# PWR-LM2941S.net
KiCad netlist of a schematic drawn in Altium Designer
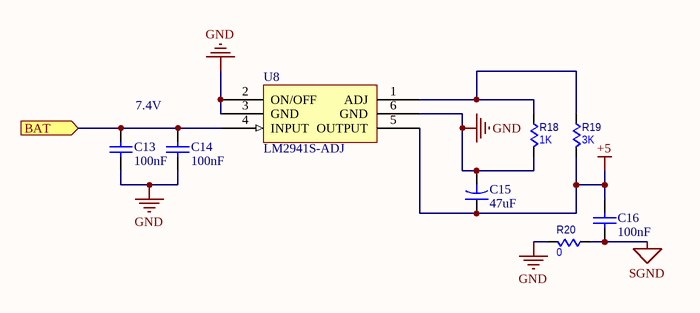
[diagram p0: PWR-LM2941S.SchDoc]

(export (version "E")
  (design (tool "Eeschema 10.0.6"))
  (components
    (comp (ref "C13")
      (value "100nF")
      (footprint "0603")
      (description "无极性电容")
      (fields (field (name "Comment") "Cap") (field (name "PUBLISHER") "Altium Limited"))
      (libsource (lib "haoze") (part "Cap"))
    )
    (comp (ref "C14")
      (value "100nF")
      (footprint "0603")
      (description "无极性电容")
      (fields (field (name "Comment") "Cap") (field (name "PUBLISHER") "Altium Limited"))
      (libsource (lib "haoze") (part "Cap"))
    )
    (comp (ref "C15")
      (value "47uF")
      (footprint "Cap-47uF")
      (description "Capacitor")
      (fields (field (name "Comment") "Cap Pol") (field (name "PUBLISHER") "Altium Limited"))
      (libsource (lib "haoze") (part "Cap Pol"))
    )
    (comp (ref "C16")
      (value "100nF")
      (footprint "0603")
      (description "无极性电容")
      (fields (field (name "Comment") "Cap") (field (name "PUBLISHER") "Altium Limited"))
      (libsource (lib "haoze") (part "Cap"))
    )
    (comp (ref "R18")
      (value "1K")
      (footprint "0603")
      (description "常规电阻")
      (fields (field (name "Comment") "Res"))
      (libsource (lib "haoze") (part "Res"))
    )
    (comp (ref "R19")
      (value "3K")
      (footprint "0603")
      (description "常规电阻")
      (fields (field (name "Comment") "Res"))
      (libsource (lib "haoze") (part "Res"))
    )
    (comp (ref "R20")
      (value "0")
      (footprint "0603")
      (description "常规电阻")
      (fields (field (name "Comment") "Res"))
      (libsource (lib "haoze") (part "Res"))
    )
    (comp (ref "U8") (value "LM2941S-ADJ") (footprint "TO263-5") (libsource (lib "haoze") (part "LM2941S")))
  )
  (nets
    (net (code "1") (name "+5") (class "Default")
      (node (ref "C15") (pin "1") (pinfunction "1_1") (pintype "passive"))
      (node (ref "C16") (pin "2") (pinfunction "2_2") (pintype "passive"))
      (node (ref "R19") (pin "2") (pinfunction "2_2") (pintype "passive"))
      (node (ref "U8") (pin "5") (pinfunction "OUTPUT_5") (pintype "passive"))
    )
    (net (code "2") (name "/BAT") (class "Default")
      (node (ref "C13") (pin "2") (pinfunction "2_2") (pintype "passive"))
      (node (ref "C14") (pin "2") (pinfunction "2_2") (pintype "passive"))
      (node (ref "U8") (pin "4") (pinfunction "INPUT_4") (pintype "input"))
    )
    (net (code "3") (name "GND") (class "Default")
      (node (ref "C13") (pin "1") (pinfunction "1_1") (pintype "passive"))
      (node (ref "C14") (pin "1") (pinfunction "1_1") (pintype "passive"))
      (node (ref "C15") (pin "2") (pinfunction "2_2") (pintype "passive"))
      (node (ref "R18") (pin "2") (pinfunction "2_2") (pintype "passive"))
      (node (ref "R20") (pin "2") (pinfunction "2_2") (pintype "passive"))
      (node (ref "U8") (pin "2") (pinfunction "ON/OFF_2") (pintype "passive"))
      (node (ref "U8") (pin "3") (pinfunction "GND_3") (pintype "power_in"))
      (node (ref "U8") (pin "6") (pinfunction "GND_6") (pintype "power_in"))
    )
    (net (code "4") (name "Net-(U8-ADJ)") (class "Default")
      (node (ref "R18") (pin "1") (pinfunction "1_1") (pintype "passive"))
      (node (ref "R19") (pin "1") (pinfunction "1_1") (pintype "passive"))
      (node (ref "U8") (pin "1") (pinfunction "ADJ_1") (pintype "passive"))
    )
    (net (code "5") (name "SGND") (class "Default")
      (node (ref "C16") (pin "1") (pinfunction "1_1") (pintype "passive"))
      (node (ref "R20") (pin "1") (pinfunction "1_1") (pintype "passive"))
    )
  )
)
